# 2_pure60-matrix.net
KiCad netlist of a schematic drawn in Altium Designer
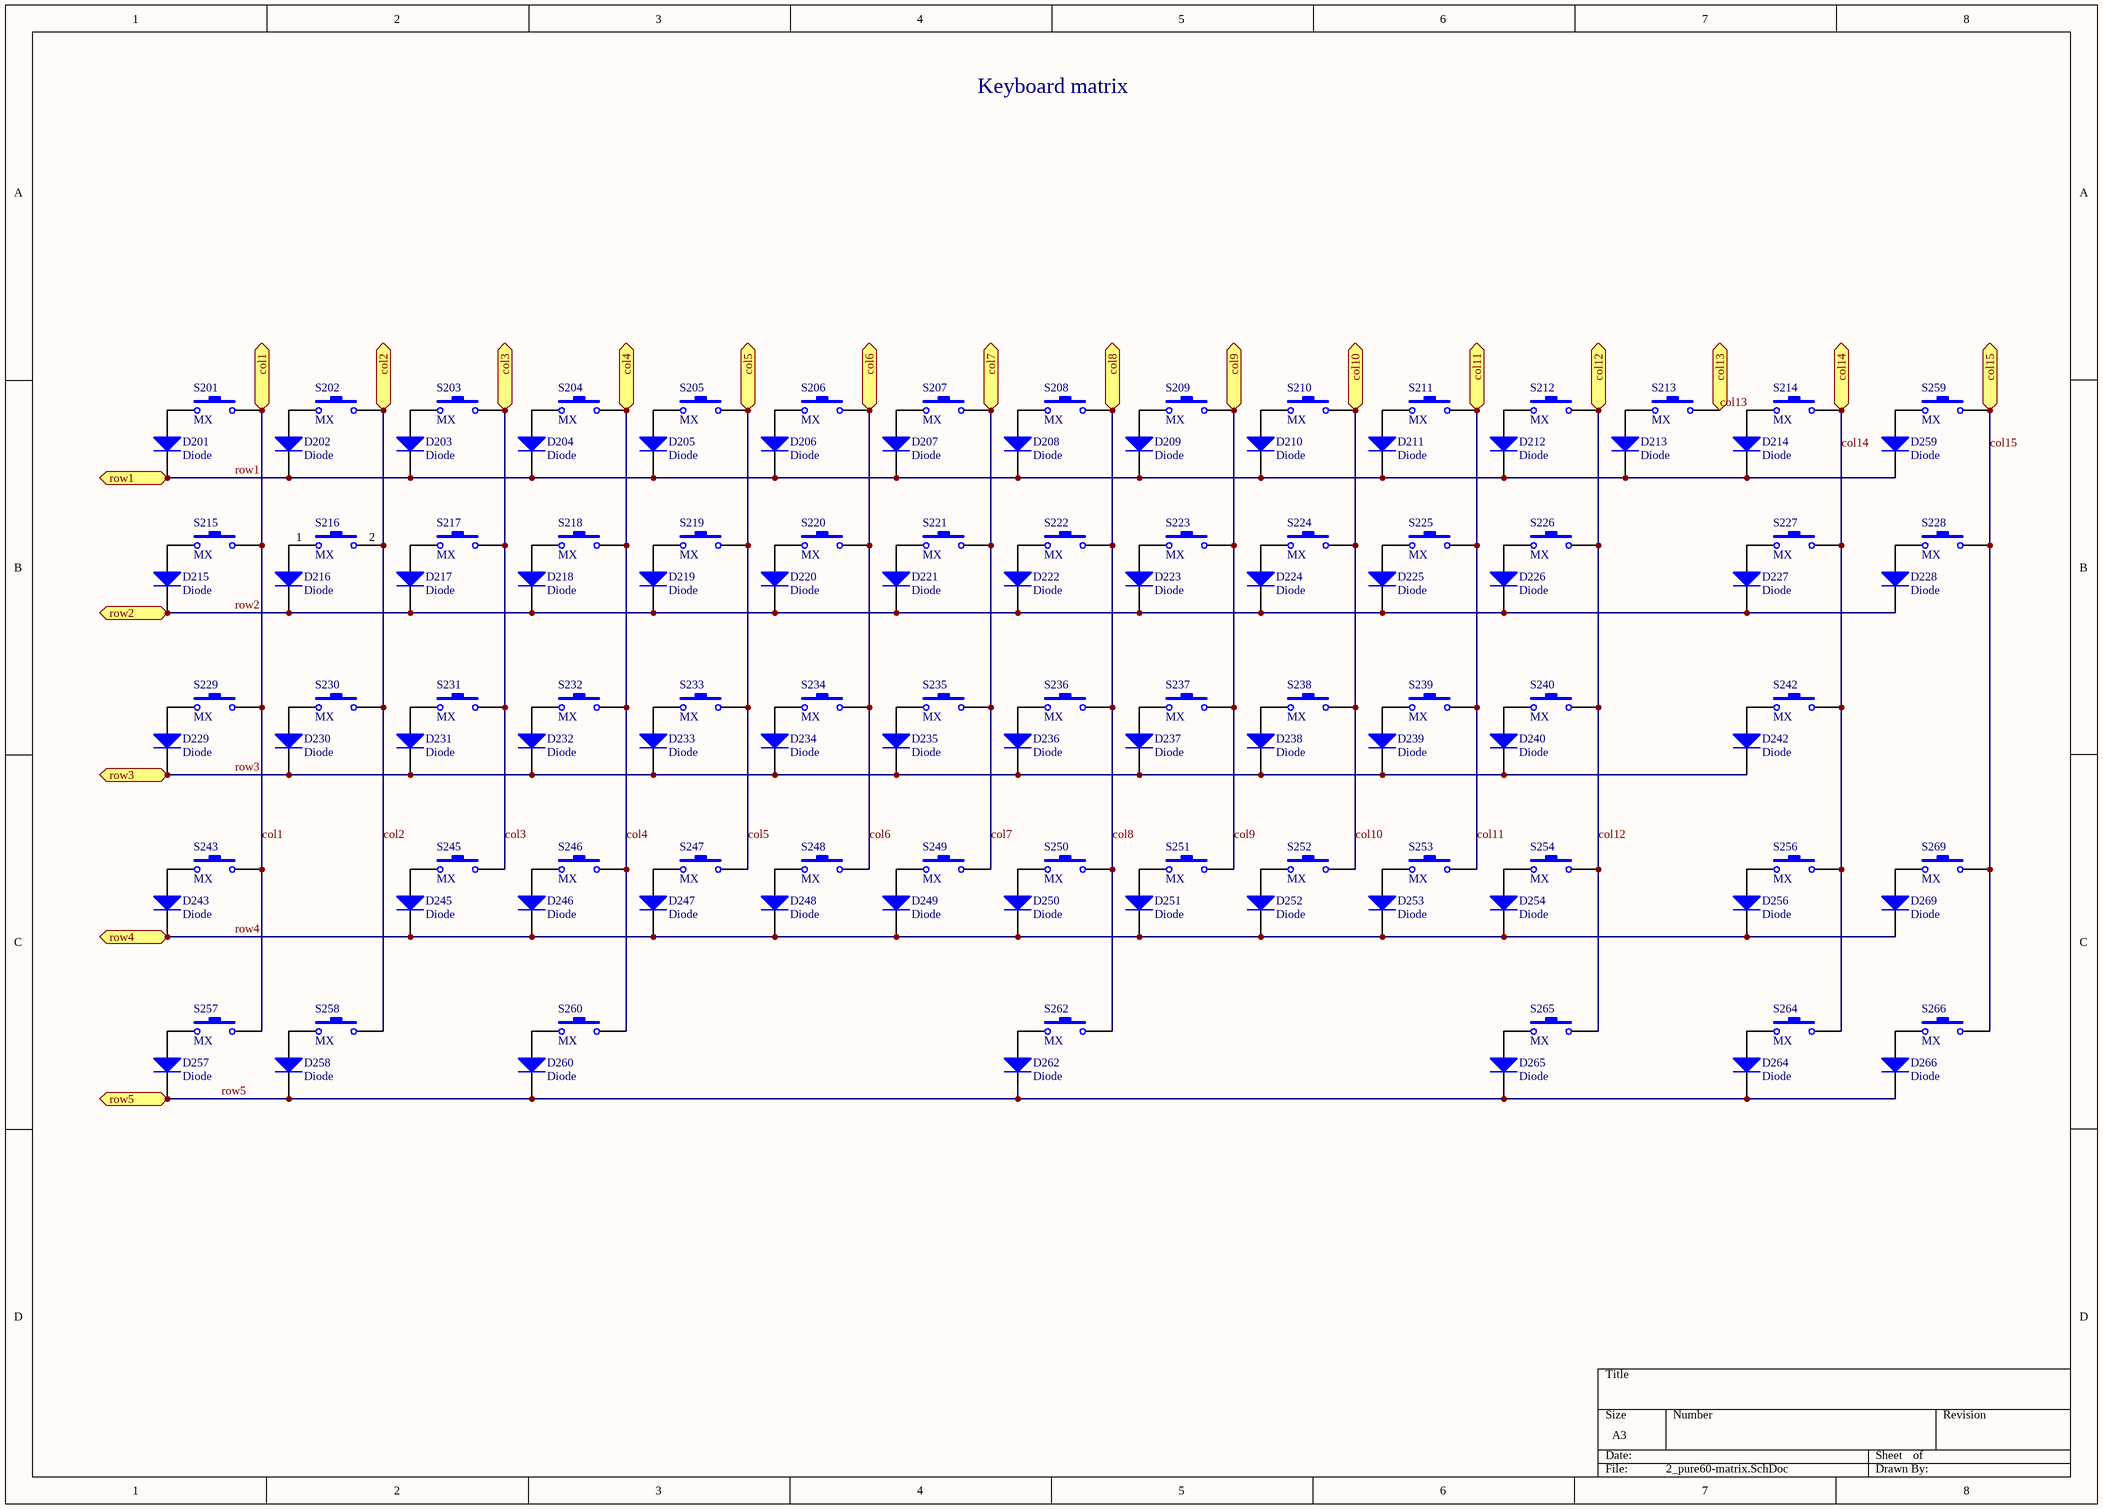
[diagram p0: 2_pure60-matrix.SchDoc]

(export (version "E")
  (design (tool "Eeschema 10.0.6"))
  (components
    (comp (ref "D201")
      (value "Diode")
      (footprint "D0603[1608]")
      (description "Default Diode")
      (fields (field (name "MFG") "Bourns Inc.") (field (name "MRF.PART") "CD4148WTP"))
      (libsource (lib "Miscellaneous Devices") (part "Diode"))
    )
    (comp (ref "D202")
      (value "Diode")
      (footprint "D0603[1608]")
      (description "Default Diode")
      (fields (field (name "MFG") "Bourns Inc.") (field (name "MRF.PART") "CD4148WTP"))
      (libsource (lib "Miscellaneous Devices") (part "Diode"))
    )
    (comp (ref "D203")
      (value "Diode")
      (footprint "D0603[1608]")
      (description "Default Diode")
      (fields (field (name "MFG") "Bourns Inc.") (field (name "MRF.PART") "CD4148WTP"))
      (libsource (lib "Miscellaneous Devices") (part "Diode"))
    )
    (comp (ref "D204")
      (value "Diode")
      (footprint "D0603[1608]")
      (description "Default Diode")
      (fields (field (name "MFG") "Bourns Inc.") (field (name "MRF.PART") "CD4148WTP"))
      (libsource (lib "Miscellaneous Devices") (part "Diode"))
    )
    (comp (ref "D205")
      (value "Diode")
      (footprint "D0603[1608]")
      (description "Default Diode")
      (fields (field (name "MFG") "Bourns Inc.") (field (name "MRF.PART") "CD4148WTP"))
      (libsource (lib "Miscellaneous Devices") (part "Diode"))
    )
    (comp (ref "D206")
      (value "Diode")
      (footprint "D0603[1608]")
      (description "Default Diode")
      (fields (field (name "MFG") "Bourns Inc.") (field (name "MRF.PART") "CD4148WTP"))
      (libsource (lib "Miscellaneous Devices") (part "Diode"))
    )
    (comp (ref "D207")
      (value "Diode")
      (footprint "D0603[1608]")
      (description "Default Diode")
      (fields (field (name "MFG") "Bourns Inc.") (field (name "MRF.PART") "CD4148WTP"))
      (libsource (lib "Miscellaneous Devices") (part "Diode"))
    )
    (comp (ref "D208")
      (value "Diode")
      (footprint "D0603[1608]")
      (description "Default Diode")
      (fields (field (name "MFG") "Bourns Inc.") (field (name "MRF.PART") "CD4148WTP"))
      (libsource (lib "Miscellaneous Devices") (part "Diode"))
    )
    (comp (ref "D209")
      (value "Diode")
      (footprint "D0603[1608]")
      (description "Default Diode")
      (fields (field (name "MFG") "Bourns Inc.") (field (name "MRF.PART") "CD4148WTP"))
      (libsource (lib "Miscellaneous Devices") (part "Diode"))
    )
    (comp (ref "D210")
      (value "Diode")
      (footprint "D0603[1608]")
      (description "Default Diode")
      (fields (field (name "MFG") "Bourns Inc.") (field (name "MRF.PART") "CD4148WTP"))
      (libsource (lib "Miscellaneous Devices") (part "Diode"))
    )
    (comp (ref "D211")
      (value "Diode")
      (footprint "D0603[1608]")
      (description "Default Diode")
      (fields (field (name "MFG") "Bourns Inc.") (field (name "MRF.PART") "CD4148WTP"))
      (libsource (lib "Miscellaneous Devices") (part "Diode"))
    )
    (comp (ref "D212")
      (value "Diode")
      (footprint "D0603[1608]")
      (description "Default Diode")
      (fields (field (name "MFG") "Bourns Inc.") (field (name "MRF.PART") "CD4148WTP"))
      (libsource (lib "Miscellaneous Devices") (part "Diode"))
    )
    (comp (ref "D213")
      (value "Diode")
      (footprint "D0603[1608]")
      (description "Default Diode")
      (fields (field (name "MFG") "Bourns Inc.") (field (name "MRF.PART") "CD4148WTP"))
      (libsource (lib "Miscellaneous Devices") (part "Diode"))
    )
    (comp (ref "D214")
      (value "Diode")
      (footprint "D0603[1608]")
      (description "Default Diode")
      (fields (field (name "MFG") "Bourns Inc.") (field (name "MRF.PART") "CD4148WTP"))
      (libsource (lib "Miscellaneous Devices") (part "Diode"))
    )
    (comp (ref "D215")
      (value "Diode")
      (footprint "D0603[1608]")
      (description "Default Diode")
      (fields (field (name "MFG") "Bourns Inc.") (field (name "MRF.PART") "CD4148WTP"))
      (libsource (lib "Miscellaneous Devices") (part "Diode"))
    )
    (comp (ref "D216")
      (value "Diode")
      (footprint "D0603[1608]")
      (description "Default Diode")
      (fields (field (name "MFG") "Bourns Inc.") (field (name "MRF.PART") "CD4148WTP"))
      (libsource (lib "Miscellaneous Devices") (part "Diode"))
    )
    (comp (ref "D217")
      (value "Diode")
      (footprint "D0603[1608]")
      (description "Default Diode")
      (fields (field (name "MFG") "Bourns Inc.") (field (name "MRF.PART") "CD4148WTP"))
      (libsource (lib "Miscellaneous Devices") (part "Diode"))
    )
    (comp (ref "D218")
      (value "Diode")
      (footprint "D0603[1608]")
      (description "Default Diode")
      (fields (field (name "MFG") "Bourns Inc.") (field (name "MRF.PART") "CD4148WTP"))
      (libsource (lib "Miscellaneous Devices") (part "Diode"))
    )
    (comp (ref "D219")
      (value "Diode")
      (footprint "D0603[1608]")
      (description "Default Diode")
      (fields (field (name "MFG") "Bourns Inc.") (field (name "MRF.PART") "CD4148WTP"))
      (libsource (lib "Miscellaneous Devices") (part "Diode"))
    )
    (comp (ref "D220")
      (value "Diode")
      (footprint "D0603[1608]")
      (description "Default Diode")
      (fields (field (name "MFG") "Bourns Inc.") (field (name "MRF.PART") "CD4148WTP"))
      (libsource (lib "Miscellaneous Devices") (part "Diode"))
    )
    (comp (ref "D221")
      (value "Diode")
      (footprint "D0603[1608]")
      (description "Default Diode")
      (fields (field (name "MFG") "Bourns Inc.") (field (name "MRF.PART") "CD4148WTP"))
      (libsource (lib "Miscellaneous Devices") (part "Diode"))
    )
    (comp (ref "D222")
      (value "Diode")
      (footprint "D0603[1608]")
      (description "Default Diode")
      (fields (field (name "MFG") "Bourns Inc.") (field (name "MRF.PART") "CD4148WTP"))
      (libsource (lib "Miscellaneous Devices") (part "Diode"))
    )
    (comp (ref "D223")
      (value "Diode")
      (footprint "D0603[1608]")
      (description "Default Diode")
      (fields (field (name "MFG") "Bourns Inc.") (field (name "MRF.PART") "CD4148WTP"))
      (libsource (lib "Miscellaneous Devices") (part "Diode"))
    )
    (comp (ref "D224")
      (value "Diode")
      (footprint "D0603[1608]")
      (description "Default Diode")
      (fields (field (name "MFG") "Bourns Inc.") (field (name "MRF.PART") "CD4148WTP"))
      (libsource (lib "Miscellaneous Devices") (part "Diode"))
    )
    (comp (ref "D225")
      (value "Diode")
      (footprint "D0603[1608]")
      (description "Default Diode")
      (fields (field (name "MFG") "Bourns Inc.") (field (name "MRF.PART") "CD4148WTP"))
      (libsource (lib "Miscellaneous Devices") (part "Diode"))
    )
    (comp (ref "D226")
      (value "Diode")
      (footprint "D0603[1608]")
      (description "Default Diode")
      (fields (field (name "MFG") "Bourns Inc.") (field (name "MRF.PART") "CD4148WTP"))
      (libsource (lib "Miscellaneous Devices") (part "Diode"))
    )
    (comp (ref "D227")
      (value "Diode")
      (footprint "D0603[1608]")
      (description "Default Diode")
      (fields (field (name "MFG") "Bourns Inc.") (field (name "MRF.PART") "CD4148WTP"))
      (libsource (lib "Miscellaneous Devices") (part "Diode"))
    )
    (comp (ref "D228")
      (value "Diode")
      (footprint "D0603[1608]")
      (description "Default Diode")
      (fields (field (name "MFG") "Bourns Inc.") (field (name "MRF.PART") "CD4148WTP"))
      (libsource (lib "Miscellaneous Devices") (part "Diode"))
    )
    (comp (ref "D229")
      (value "Diode")
      (footprint "D0603[1608]")
      (description "Default Diode")
      (fields (field (name "MFG") "Bourns Inc.") (field (name "MRF.PART") "CD4148WTP"))
      (libsource (lib "Miscellaneous Devices") (part "Diode"))
    )
    (comp (ref "D230")
      (value "Diode")
      (footprint "D0603[1608]")
      (description "Default Diode")
      (fields (field (name "MFG") "Bourns Inc.") (field (name "MRF.PART") "CD4148WTP"))
      (libsource (lib "Miscellaneous Devices") (part "Diode"))
    )
    (comp (ref "D231")
      (value "Diode")
      (footprint "D0603[1608]")
      (description "Default Diode")
      (fields (field (name "MFG") "Bourns Inc.") (field (name "MRF.PART") "CD4148WTP"))
      (libsource (lib "Miscellaneous Devices") (part "Diode"))
    )
    (comp (ref "D232")
      (value "Diode")
      (footprint "D0603[1608]")
      (description "Default Diode")
      (fields (field (name "MFG") "Bourns Inc.") (field (name "MRF.PART") "CD4148WTP"))
      (libsource (lib "Miscellaneous Devices") (part "Diode"))
    )
    (comp (ref "D233")
      (value "Diode")
      (footprint "D0603[1608]")
      (description "Default Diode")
      (fields (field (name "MFG") "Bourns Inc.") (field (name "MRF.PART") "CD4148WTP"))
      (libsource (lib "Miscellaneous Devices") (part "Diode"))
    )
    (comp (ref "D234")
      (value "Diode")
      (footprint "D0603[1608]")
      (description "Default Diode")
      (fields (field (name "MFG") "Bourns Inc.") (field (name "MRF.PART") "CD4148WTP"))
      (libsource (lib "Miscellaneous Devices") (part "Diode"))
    )
    (comp (ref "D235")
      (value "Diode")
      (footprint "D0603[1608]")
      (description "Default Diode")
      (fields (field (name "MFG") "Bourns Inc.") (field (name "MRF.PART") "CD4148WTP"))
      (libsource (lib "Miscellaneous Devices") (part "Diode"))
    )
    (comp (ref "D236")
      (value "Diode")
      (footprint "D0603[1608]")
      (description "Default Diode")
      (fields (field (name "MFG") "Bourns Inc.") (field (name "MRF.PART") "CD4148WTP"))
      (libsource (lib "Miscellaneous Devices") (part "Diode"))
    )
    (comp (ref "D237")
      (value "Diode")
      (footprint "D0603[1608]")
      (description "Default Diode")
      (fields (field (name "MFG") "Bourns Inc.") (field (name "MRF.PART") "CD4148WTP"))
      (libsource (lib "Miscellaneous Devices") (part "Diode"))
    )
    (comp (ref "D238")
      (value "Diode")
      (footprint "D0603[1608]")
      (description "Default Diode")
      (fields (field (name "MFG") "Bourns Inc.") (field (name "MRF.PART") "CD4148WTP"))
      (libsource (lib "Miscellaneous Devices") (part "Diode"))
    )
    (comp (ref "D239")
      (value "Diode")
      (footprint "D0603[1608]")
      (description "Default Diode")
      (fields (field (name "MFG") "Bourns Inc.") (field (name "MRF.PART") "CD4148WTP"))
      (libsource (lib "Miscellaneous Devices") (part "Diode"))
    )
    (comp (ref "D240")
      (value "Diode")
      (footprint "D0603[1608]")
      (description "Default Diode")
      (fields (field (name "MFG") "Bourns Inc.") (field (name "MRF.PART") "CD4148WTP"))
      (libsource (lib "Miscellaneous Devices") (part "Diode"))
    )
    (comp (ref "D242")
      (value "Diode")
      (footprint "D0603[1608]")
      (description "Default Diode")
      (fields (field (name "MFG") "Bourns Inc.") (field (name "MRF.PART") "CD4148WTP"))
      (libsource (lib "Miscellaneous Devices") (part "Diode"))
    )
    (comp (ref "D243")
      (value "Diode")
      (footprint "D0603[1608]")
      (description "Default Diode")
      (fields (field (name "MFG") "Bourns Inc.") (field (name "MRF.PART") "CD4148WTP"))
      (libsource (lib "Miscellaneous Devices") (part "Diode"))
    )
    (comp (ref "D245")
      (value "Diode")
      (footprint "D0603[1608]")
      (description "Default Diode")
      (fields (field (name "MFG") "Bourns Inc.") (field (name "MRF.PART") "CD4148WTP"))
      (libsource (lib "Miscellaneous Devices") (part "Diode"))
    )
    (comp (ref "D246")
      (value "Diode")
      (footprint "D0603[1608]")
      (description "Default Diode")
      (fields (field (name "MFG") "Bourns Inc.") (field (name "MRF.PART") "CD4148WTP"))
      (libsource (lib "Miscellaneous Devices") (part "Diode"))
    )
    (comp (ref "D247")
      (value "Diode")
      (footprint "D0603[1608]")
      (description "Default Diode")
      (fields (field (name "MFG") "Bourns Inc.") (field (name "MRF.PART") "CD4148WTP"))
      (libsource (lib "Miscellaneous Devices") (part "Diode"))
    )
    (comp (ref "D248")
      (value "Diode")
      (footprint "D0603[1608]")
      (description "Default Diode")
      (fields (field (name "MFG") "Bourns Inc.") (field (name "MRF.PART") "CD4148WTP"))
      (libsource (lib "Miscellaneous Devices") (part "Diode"))
    )
    (comp (ref "D249")
      (value "Diode")
      (footprint "D0603[1608]")
      (description "Default Diode")
      (fields (field (name "MFG") "Bourns Inc.") (field (name "MRF.PART") "CD4148WTP"))
      (libsource (lib "Miscellaneous Devices") (part "Diode"))
    )
    (comp (ref "D250")
      (value "Diode")
      (footprint "D0603[1608]")
      (description "Default Diode")
      (fields (field (name "MFG") "Bourns Inc.") (field (name "MRF.PART") "CD4148WTP"))
      (libsource (lib "Miscellaneous Devices") (part "Diode"))
    )
    (comp (ref "D251")
      (value "Diode")
      (footprint "D0603[1608]")
      (description "Default Diode")
      (fields (field (name "MFG") "Bourns Inc.") (field (name "MRF.PART") "CD4148WTP"))
      (libsource (lib "Miscellaneous Devices") (part "Diode"))
    )
    (comp (ref "D252")
      (value "Diode")
      (footprint "D0603[1608]")
      (description "Default Diode")
      (fields (field (name "MFG") "Bourns Inc.") (field (name "MRF.PART") "CD4148WTP"))
      (libsource (lib "Miscellaneous Devices") (part "Diode"))
    )
    (comp (ref "D253")
      (value "Diode")
      (footprint "D0603[1608]")
      (description "Default Diode")
      (fields (field (name "MFG") "Bourns Inc.") (field (name "MRF.PART") "CD4148WTP"))
      (libsource (lib "Miscellaneous Devices") (part "Diode"))
    )
    (comp (ref "D254")
      (value "Diode")
      (footprint "D0603[1608]")
      (description "Default Diode")
      (fields (field (name "MFG") "Bourns Inc.") (field (name "MRF.PART") "CD4148WTP"))
      (libsource (lib "Miscellaneous Devices") (part "Diode"))
    )
    (comp (ref "D256")
      (value "Diode")
      (footprint "D0603[1608]")
      (description "Default Diode")
      (fields (field (name "MFG") "Bourns Inc.") (field (name "MRF.PART") "CD4148WTP"))
      (libsource (lib "Miscellaneous Devices") (part "Diode"))
    )
    (comp (ref "D257")
      (value "Diode")
      (footprint "D0603[1608]")
      (description "Default Diode")
      (fields (field (name "MFG") "Bourns Inc.") (field (name "MRF.PART") "CD4148WTP"))
      (libsource (lib "Miscellaneous Devices") (part "Diode"))
    )
    (comp (ref "D258")
      (value "Diode")
      (footprint "D0603[1608]")
      (description "Default Diode")
      (fields (field (name "MFG") "Bourns Inc.") (field (name "MRF.PART") "CD4148WTP"))
      (libsource (lib "Miscellaneous Devices") (part "Diode"))
    )
    (comp (ref "D259")
      (value "Diode")
      (footprint "D0603[1608]")
      (description "Default Diode")
      (fields (field (name "MFG") "Bourns Inc.") (field (name "MRF.PART") "CD4148WTP"))
      (libsource (lib "Miscellaneous Devices") (part "Diode"))
    )
    (comp (ref "D260")
      (value "Diode")
      (footprint "D0603[1608]")
      (description "Default Diode")
      (fields (field (name "MFG") "Bourns Inc.") (field (name "MRF.PART") "CD4148WTP"))
      (libsource (lib "Miscellaneous Devices") (part "Diode"))
    )
    (comp (ref "D262")
      (value "Diode")
      (footprint "D0603[1608]")
      (description "Default Diode")
      (fields (field (name "MFG") "Bourns Inc.") (field (name "MRF.PART") "CD4148WTP"))
      (libsource (lib "Miscellaneous Devices") (part "Diode"))
    )
    (comp (ref "D264")
      (value "Diode")
      (footprint "D0603[1608]")
      (description "Default Diode")
      (fields (field (name "MFG") "Bourns Inc.") (field (name "MRF.PART") "CD4148WTP"))
      (libsource (lib "Miscellaneous Devices") (part "Diode"))
    )
    (comp (ref "D265")
      (value "Diode")
      (footprint "D0603[1608]")
      (description "Default Diode")
      (fields (field (name "MFG") "Bourns Inc.") (field (name "MRF.PART") "CD4148WTP"))
      (libsource (lib "Miscellaneous Devices") (part "Diode"))
    )
    (comp (ref "D266")
      (value "Diode")
      (footprint "D0603[1608]")
      (description "Default Diode")
      (fields (field (name "MFG") "Bourns Inc.") (field (name "MRF.PART") "CD4148WTP"))
      (libsource (lib "Miscellaneous Devices") (part "Diode"))
    )
    (comp (ref "D269")
      (value "Diode")
      (footprint "D0603[1608]")
      (description "Default Diode")
      (fields (field (name "MFG") "Bourns Inc.") (field (name "MRF.PART") "CD4148WTP"))
      (libsource (lib "Miscellaneous Devices") (part "Diode"))
    )
    (comp (ref "S201")
      (value "MX")
      (footprint "MX-switch - switched pol")
      (description "Switch")
      (libsource (lib "Miscellaneous Devices") (part "SW-PB"))
    )
    (comp (ref "S202")
      (value "MX")
      (footprint "MX-switch - switched pol")
      (description "Switch")
      (libsource (lib "Miscellaneous Devices") (part "SW-PB"))
    )
    (comp (ref "S203")
      (value "MX")
      (footprint "MX-switch - switched pol")
      (description "Switch")
      (libsource (lib "Miscellaneous Devices") (part "SW-PB"))
    )
    (comp (ref "S204")
      (value "MX")
      (footprint "MX-switch - switched pol")
      (description "Switch")
      (libsource (lib "Miscellaneous Devices") (part "SW-PB"))
    )
    (comp (ref "S205")
      (value "MX")
      (footprint "MX-switch - switched pol")
      (description "Switch")
      (libsource (lib "Miscellaneous Devices") (part "SW-PB"))
    )
    (comp (ref "S206")
      (value "MX")
      (footprint "MX-switch - switched pol")
      (description "Switch")
      (libsource (lib "Miscellaneous Devices") (part "SW-PB"))
    )
    (comp (ref "S207")
      (value "MX")
      (footprint "MX-switch - switched pol")
      (description "Switch")
      (libsource (lib "Miscellaneous Devices") (part "SW-PB"))
    )
    (comp (ref "S208")
      (value "MX")
      (footprint "MX-switch - switched pol")
      (description "Switch")
      (libsource (lib "Miscellaneous Devices") (part "SW-PB"))
    )
    (comp (ref "S209")
      (value "MX")
      (footprint "MX-switch - switched pol")
      (description "Switch")
      (libsource (lib "Miscellaneous Devices") (part "SW-PB"))
    )
    (comp (ref "S210")
      (value "MX")
      (footprint "MX-switch - switched pol")
      (description "Switch")
      (libsource (lib "Miscellaneous Devices") (part "SW-PB"))
    )
    (comp (ref "S211")
      (value "MX")
      (footprint "MX-switch - switched pol")
      (description "Switch")
      (libsource (lib "Miscellaneous Devices") (part "SW-PB"))
    )
    (comp (ref "S212")
      (value "MX")
      (footprint "MX-switch - switched pol")
      (description "Switch")
      (libsource (lib "Miscellaneous Devices") (part "SW-PB"))
    )
    (comp (ref "S213")
      (value "MX")
      (footprint "MX-switch - switched pol")
      (description "Switch")
      (libsource (lib "Miscellaneous Devices") (part "SW-PB"))
    )
    (comp (ref "S214")
      (value "MX")
      (footprint "MX-switch - switched pol")
      (description "Switch")
      (libsource (lib "Miscellaneous Devices") (part "SW-PB"))
    )
    (comp (ref "S215")
      (value "MX")
      (footprint "MX-switch - 1.5U - switched pol")
      (description "TAB")
      (libsource (lib "Miscellaneous Devices") (part "SW-PB"))
    )
    (comp (ref "S216")
      (value "MX")
      (footprint "MX-switch - switched pol")
      (description "Switch")
      (libsource (lib "") (part "SW-PB_1"))
    )
    (comp (ref "S217")
      (value "MX")
      (footprint "MX-switch - switched pol")
      (description "Switch")
      (libsource (lib "Miscellaneous Devices") (part "SW-PB"))
    )
    (comp (ref "S218")
      (value "MX")
      (footprint "MX-switch - switched pol")
      (description "Switch")
      (libsource (lib "Miscellaneous Devices") (part "SW-PB"))
    )
    (comp (ref "S219")
      (value "MX")
      (footprint "MX-switch - switched pol")
      (description "Switch")
      (libsource (lib "Miscellaneous Devices") (part "SW-PB"))
    )
    (comp (ref "S220")
      (value "MX")
      (footprint "MX-switch - switched pol")
      (description "Switch")
      (libsource (lib "Miscellaneous Devices") (part "SW-PB"))
    )
    (comp (ref "S221")
      (value "MX")
      (footprint "MX-switch - switched pol")
      (description "Switch")
      (libsource (lib "Miscellaneous Devices") (part "SW-PB"))
    )
    (comp (ref "S222")
      (value "MX")
      (footprint "MX-switch - switched pol")
      (description "Switch")
      (libsource (lib "Miscellaneous Devices") (part "SW-PB"))
    )
    (comp (ref "S223")
      (value "MX")
      (footprint "MX-switch - switched pol")
      (description "Switch")
      (libsource (lib "Miscellaneous Devices") (part "SW-PB"))
    )
    (comp (ref "S224")
      (value "MX")
      (footprint "MX-switch - switched pol")
      (description "Switch")
      (libsource (lib "Miscellaneous Devices") (part "SW-PB"))
    )
    (comp (ref "S225")
      (value "MX")
      (footprint "MX-switch - switched pol")
      (description "Switch")
      (libsource (lib "Miscellaneous Devices") (part "SW-PB"))
    )
    (comp (ref "S226")
      (value "MX")
      (footprint "MX-switch - switched pol")
      (description "Switch")
      (libsource (lib "Miscellaneous Devices") (part "SW-PB"))
    )
    (comp (ref "S227")
      (value "MX")
      (footprint "MX-switch - switched pol")
      (description "Switch")
      (libsource (lib "Miscellaneous Devices") (part "SW-PB"))
    )
    (comp (ref "S228")
      (value "MX")
      (footprint "MX-switch - 1.5U")
      (description "Switch")
      (libsource (lib "Miscellaneous Devices") (part "SW-PB"))
    )
    (comp (ref "S229")
      (value "MX")
      (footprint "MX-switch - CAPS - stepped")
      (description "Switch")
      (libsource (lib "Miscellaneous Devices") (part "SW-PB"))
    )
    (comp (ref "S230")
      (value "MX")
      (footprint "MX-switch - switched pol")
      (description "Switch")
      (libsource (lib "Miscellaneous Devices") (part "SW-PB"))
    )
    (comp (ref "S231")
      (value "MX")
      (footprint "MX-switch - switched pol")
      (description "Switch")
      (libsource (lib "Miscellaneous Devices") (part "SW-PB"))
    )
    (comp (ref "S232")
      (value "MX")
      (footprint "MX-switch - switched pol")
      (description "Switch")
      (libsource (lib "Miscellaneous Devices") (part "SW-PB"))
    )
    (comp (ref "S233")
      (value "MX")
      (footprint "MX-switch - switched pol")
      (description "Switch")
      (libsource (lib "Miscellaneous Devices") (part "SW-PB"))
    )
    (comp (ref "S234")
      (value "MX")
      (footprint "MX-switch - switched pol")
      (description "Switch")
      (libsource (lib "Miscellaneous Devices") (part "SW-PB"))
    )
    (comp (ref "S235")
      (value "MX")
      (footprint "MX-switch - switched pol")
      (description "Switch")
      (libsource (lib "Miscellaneous Devices") (part "SW-PB"))
    )
    (comp (ref "S236")
      (value "MX")
      (footprint "MX-switch - switched pol")
      (description "Switch")
      (libsource (lib "Miscellaneous Devices") (part "SW-PB"))
    )
    (comp (ref "S237")
      (value "MX")
      (footprint "MX-switch - switched pol")
      (description "Switch")
      (libsource (lib "Miscellaneous Devices") (part "SW-PB"))
    )
    (comp (ref "S238")
      (value "MX")
      (footprint "MX-switch - switched pol")
      (description "Switch")
      (libsource (lib "Miscellaneous Devices") (part "SW-PB"))
    )
    (comp (ref "S239")
      (value "MX")
      (footprint "MX-switch - switched pol")
      (description "Switch")
      (libsource (lib "Miscellaneous Devices") (part "SW-PB"))
    )
    (comp (ref "S240")
      (value "MX")
      (footprint "MX-switch - switched pol")
      (description "Switch")
      (libsource (lib "Miscellaneous Devices") (part "SW-PB"))
    )
    (comp (ref "S242")
      (value "MX")
      (footprint "MX-switch - Enter_ANSI")
      (description "Switch")
      (libsource (lib "Miscellaneous Devices") (part "SW-PB"))
    )
    (comp (ref "S243")
      (value "MX")
      (footprint "MX-switch - 2.25U")
      (description "Switch")
      (libsource (lib "Miscellaneous Devices") (part "SW-PB"))
    )
    (comp (ref "S245")
      (value "MX")
      (footprint "MX-switch - switched pol")
      (description "Switch")
      (libsource (lib "Miscellaneous Devices") (part "SW-PB"))
    )
    (comp (ref "S246")
      (value "MX")
      (footprint "MX-switch - switched pol")
      (description "Switch")
      (libsource (lib "Miscellaneous Devices") (part "SW-PB"))
    )
    (comp (ref "S247")
      (value "MX")
      (footprint "MX-switch - switched pol")
      (description "Switch")
      (libsource (lib "Miscellaneous Devices") (part "SW-PB"))
    )
    (comp (ref "S248")
      (value "MX")
      (footprint "MX-switch - switched pol")
      (description "Switch")
      (libsource (lib "Miscellaneous Devices") (part "SW-PB"))
    )
    (comp (ref "S249")
      (value "MX")
      (footprint "MX-switch - switched pol")
      (description "Switch")
      (libsource (lib "Miscellaneous Devices") (part "SW-PB"))
    )
    (comp (ref "S250")
      (value "MX")
      (footprint "MX-switch - switched pol")
      (description "Switch")
      (libsource (lib "Miscellaneous Devices") (part "SW-PB"))
    )
    (comp (ref "S251")
      (value "MX")
      (footprint "MX-switch - switched pol")
      (description "Switch")
      (libsource (lib "Miscellaneous Devices") (part "SW-PB"))
    )
    (comp (ref "S252")
      (value "MX")
      (footprint "MX-switch - switched pol")
      (description "Switch")
      (libsource (lib "Miscellaneous Devices") (part "SW-PB"))
    )
    (comp (ref "S253")
      (value "MX")
      (footprint "MX-switch - switched pol")
      (description "Switch")
      (libsource (lib "Miscellaneous Devices") (part "SW-PB"))
    )
    (comp (ref "S254")
      (value "MX")
      (footprint "MX-switch - switched pol")
      (description "Switch")
      (libsource (lib "Miscellaneous Devices") (part "SW-PB"))
    )
    (comp (ref "S256")
      (value "MX")
      (footprint "MX-switch - 1.75")
      (description "Switch")
      (libsource (lib "Miscellaneous Devices") (part "SW-PB"))
    )
    (comp (ref "S257")
      (value "MX")
      (footprint "MX-switch - 1.5U")
      (description "Switch")
      (libsource (lib "Miscellaneous Devices") (part "SW-PB"))
    )
    (comp (ref "S258")
      (value "MX")
      (footprint "MX-switch")
      (description "Switch")
      (libsource (lib "Miscellaneous Devices") (part "SW-PB"))
    )
    (comp (ref "S259")
      (value "MX")
      (footprint "MX-switch")
      (description "Switch")
      (libsource (lib "Miscellaneous Devices") (part "SW-PB"))
    )
    (comp (ref "S260")
      (value "MX")
      (footprint "MX-switch - 1.5U")
      (description "Switch")
      (libsource (lib "Miscellaneous Devices") (part "SW-PB"))
    )
    (comp (ref "S262")
      (value "MX")
      (footprint "MX-switch - 7u space")
      (description "Switch")
      (libsource (lib "Miscellaneous Devices") (part "SW-PB"))
    )
    (comp (ref "S264")
      (value "MX")
      (footprint "MX-switch")
      (description "Switch")
      (libsource (lib "Miscellaneous Devices") (part "SW-PB"))
    )
    (comp (ref "S265")
      (value "MX")
      (footprint "MX-switch - 1.5U")
      (description "Switch")
      (libsource (lib "Miscellaneous Devices") (part "SW-PB"))
    )
    (comp (ref "S266")
      (value "MX")
      (footprint "MX-switch - 1.5U")
      (description "Switch")
      (libsource (lib "Miscellaneous Devices") (part "SW-PB"))
    )
    (comp (ref "S269")
      (value "MX")
      (footprint "MX-switch")
      (description "Switch")
      (libsource (lib "Miscellaneous Devices") (part "SW-PB"))
    )
  )
  (nets
    (net (code "1") (name "/col1") (class "Default")
      (node (ref "S201") (pin "2") (pinfunction "2_2") (pintype "passive"))
      (node (ref "S215") (pin "2") (pinfunction "2_2") (pintype "passive"))
      (node (ref "S229") (pin "2") (pinfunction "2_2") (pintype "passive"))
      (node (ref "S243") (pin "2") (pinfunction "2_2") (pintype "passive"))
      (node (ref "S257") (pin "2") (pinfunction "2_2") (pintype "passive"))
    )
    (net (code "2") (name "/col2") (class "Default")
      (node (ref "S202") (pin "2") (pinfunction "2_2") (pintype "passive"))
      (node (ref "S216") (pin "2") (pinfunction "2_2") (pintype "passive"))
      (node (ref "S230") (pin "2") (pinfunction "2_2") (pintype "passive"))
      (node (ref "S258") (pin "2") (pinfunction "2_2") (pintype "passive"))
    )
    (net (code "3") (name "/col3") (class "Default")
      (node (ref "S203") (pin "2") (pinfunction "2_2") (pintype "passive"))
      (node (ref "S217") (pin "2") (pinfunction "2_2") (pintype "passive"))
      (node (ref "S231") (pin "2") (pinfunction "2_2") (pintype "passive"))
      (node (ref "S245") (pin "2") (pinfunction "2_2") (pintype "passive"))
    )
    (net (code "4") (name "/col4") (class "Default")
      (node (ref "S204") (pin "2") (pinfunction "2_2") (pintype "passive"))
      (node (ref "S218") (pin "2") (pinfunction "2_2") (pintype "passive"))
      (node (ref "S232") (pin "2") (pinfunction "2_2") (pintype "passive"))
      (node (ref "S246") (pin "2") (pinfunction "2_2") (pintype "passive"))
      (node (ref "S260") (pin "2") (pinfunction "2_2") (pintype "passive"))
    )
    (net (code "5") (name "/col5") (class "Default")
      (node (ref "S205") (pin "2") (pinfunction "2_2") (pintype "passive"))
      (node (ref "S219") (pin "2") (pinfunction "2_2") (pintype "passive"))
      (node (ref "S233") (pin "2") (pinfunction "2_2") (pintype "passive"))
      (node (ref "S247") (pin "2") (pinfunction "2_2") (pintype "passive"))
    )
    (net (code "6") (name "/col6") (class "Default")
      (node (ref "S206") (pin "2") (pinfunction "2_2") (pintype "passive"))
      (node (ref "S220") (pin "2") (pinfunction "2_2") (pintype "passive"))
      (node (ref "S234") (pin "2") (pinfunction "2_2") (pintype "passive"))
      (node (ref "S248") (pin "2") (pinfunction "2_2") (pintype "passive"))
    )
    (net (code "7") (name "/col7") (class "Default")
      (node (ref "S207") (pin "2") (pinfunction "2_2") (pintype "passive"))
      (node (ref "S221") (pin "2") (pinfunction "2_2") (pintype "passive"))
      (node (ref "S235") (pin "2") (pinfunction "2_2") (pintype "passive"))
      (node (ref "S249") (pin "2") (pinfunction "2_2") (pintype "passive"))
    )
    (net (code "8") (name "/col8") (class "Default")
      (node (ref "S208") (pin "2") (pinfunction "2_2") (pintype "passive"))
      (node (ref "S222") (pin "2") (pinfunction "2_2") (pintype "passive"))
      (node (ref "S236") (pin "2") (pinfunction "2_2") (pintype "passive"))
      (node (ref "S250") (pin "2") (pinfunction "2_2") (pintype "passive"))
      (node (ref "S262") (pin "2") (pinfunction "2_2") (pintype "passive"))
    )
    (net (code "9") (name "/col9") (class "Default")
      (node (ref "S209") (pin "2") (pinfunction "2_2") (pintype "passive"))
      (node (ref "S223") (pin "2") (pinfunction "2_2") (pintype "passive"))
      (node (ref "S237") (pin "2") (pinfunction "2_2") (pintype "passive"))
      (node (ref "S251") (pin "2") (pinfunction "2_2") (pintype "passive"))
    )
    (net (code "10") (name "/col10") (class "Default")
      (node (ref "S210") (pin "2") (pinfunction "2_2") (pintype "passive"))
      (node (ref "S224") (pin "2") (pinfunction "2_2") (pintype "passive"))
      (node (ref "S238") (pin "2") (pinfunction "2_2") (pintype "passive"))
      (node (ref "S252") (pin "2") (pinfunction "2_2") (pintype "passive"))
    )
    (net (code "11") (name "/col11") (class "Default")
      (node (ref "S211") (pin "2") (pinfunction "2_2") (pintype "passive"))
      (node (ref "S225") (pin "2") (pinfunction "2_2") (pintype "passive"))
      (node (ref "S239") (pin "2") (pinfunction "2_2") (pintype "passive"))
      (node (ref "S253") (pin "2") (pinfunction "2_2") (pintype "passive"))
    )
    (net (code "12") (name "/col12") (class "Default")
      (node (ref "S212") (pin "2") (pinfunction "2_2") (pintype "passive"))
      (node (ref "S226") (pin "2") (pinfunction "2_2") (pintype "passive"))
      (node (ref "S240") (pin "2") (pinfunction "2_2") (pintype "passive"))
      (node (ref "S254") (pin "2") (pinfunction "2_2") (pintype "passive"))
      (node (ref "S265") (pin "2") (pinfunction "2_2") (pintype "passive"))
    )
    (net (code "13") (name "/col13") (class "Default")
      (node (ref "S213") (pin "2") (pinfunction "2_2") (pintype "passive"))
    )
    (net (code "14") (name "/col14") (class "Default")
      (node (ref "S214") (pin "2") (pinfunction "2_2") (pintype "passive"))
      (node (ref "S227") (pin "2") (pinfunction "2_2") (pintype "passive"))
      (node (ref "S242") (pin "2") (pinfunction "2_2") (pintype "passive"))
      (node (ref "S256") (pin "2") (pinfunction "2_2") (pintype "passive"))
      (node (ref "S264") (pin "2") (pinfunction "2_2") (pintype "passive"))
    )
    (net (code "15") (name "/col15") (class "Default")
      (node (ref "S228") (pin "2") (pinfunction "2_2") (pintype "passive"))
      (node (ref "S259") (pin "2") (pinfunction "2_2") (pintype "passive"))
      (node (ref "S266") (pin "2") (pinfunction "2_2") (pintype "passive"))
      (node (ref "S269") (pin "2") (pinfunction "2_2") (pintype "passive"))
    )
    (net (code "16") (name "/row1") (class "Default")
      (node (ref "D201") (pin "2") (pinfunction "K_2") (pintype "passive"))
      (node (ref "D202") (pin "2") (pinfunction "K_2") (pintype "passive"))
      (node (ref "D203") (pin "2") (pinfunction "K_2") (pintype "passive"))
      (node (ref "D204") (pin "2") (pinfunction "K_2") (pintype "passive"))
      (node (ref "D205") (pin "2") (pinfunction "K_2") (pintype "passive"))
      (node (ref "D206") (pin "2") (pinfunction "K_2") (pintype "passive"))
      (node (ref "D207") (pin "2") (pinfunction "K_2") (pintype "passive"))
      (node (ref "D208") (pin "2") (pinfunction "K_2") (pintype "passive"))
      (node (ref "D209") (pin "2") (pinfunction "K_2") (pintype "passive"))
      (node (ref "D210") (pin "2") (pinfunction "K_2") (pintype "passive"))
      (node (ref "D211") (pin "2") (pinfunction "K_2") (pintype "passive"))
      (node (ref "D212") (pin "2") (pinfunction "K_2") (pintype "passive"))
      (node (ref "D213") (pin "2") (pinfunction "K_2") (pintype "passive"))
      (node (ref "D214") (pin "2") (pinfunction "K_2") (pintype "passive"))
      (node (ref "D259") (pin "2") (pinfunction "K_2") (pintype "passive"))
    )
    (net (code "17") (name "/row2") (class "Default")
      (node (ref "D215") (pin "2") (pinfunction "K_2") (pintype "passive"))
      (node (ref "D216") (pin "2") (pinfunction "K_2") (pintype "passive"))
      (node (ref "D217") (pin "2") (pinfunction "K_2") (pintype "passive"))
      (node (ref "D218") (pin "2") (pinfunction "K_2") (pintype "passive"))
      (node (ref "D219") (pin "2") (pinfunction "K_2") (pintype "passive"))
      (node (ref "D220") (pin "2") (pinfunction "K_2") (pintype "passive"))
      (node (ref "D221") (pin "2") (pinfunction "K_2") (pintype "passive"))
      (node (ref "D222") (pin "2") (pinfunction "K_2") (pintype "passive"))
      (node (ref "D223") (pin "2") (pinfunction "K_2") (pintype "passive"))
      (node (ref "D224") (pin "2") (pinfunction "K_2") (pintype "passive"))
      (node (ref "D225") (pin "2") (pinfunction "K_2") (pintype "passive"))
      (node (ref "D226") (pin "2") (pinfunction "K_2") (pintype "passive"))
      (node (ref "D227") (pin "2") (pinfunction "K_2") (pintype "passive"))
      (node (ref "D228") (pin "2") (pinfunction "K_2") (pintype "passive"))
    )
    (net (code "18") (name "/row3") (class "Default")
      (node (ref "D229") (pin "2") (pinfunction "K_2") (pintype "passive"))
      (node (ref "D230") (pin "2") (pinfunction "K_2") (pintype "passive"))
      (node (ref "D231") (pin "2") (pinfunction "K_2") (pintype "passive"))
      (node (ref "D232") (pin "2") (pinfunction "K_2") (pintype "passive"))
      (node (ref "D233") (pin "2") (pinfunction "K_2") (pintype "passive"))
      (node (ref "D234") (pin "2") (pinfunction "K_2") (pintype "passive"))
      (node (ref "D235") (pin "2") (pinfunction "K_2") (pintype "passive"))
      (node (ref "D236") (pin "2") (pinfunction "K_2") (pintype "passive"))
      (node (ref "D237") (pin "2") (pinfunction "K_2") (pintype "passive"))
      (node (ref "D238") (pin "2") (pinfunction "K_2") (pintype "passive"))
      (node (ref "D239") (pin "2") (pinfunction "K_2") (pintype "passive"))
      (node (ref "D240") (pin "2") (pinfunction "K_2") (pintype "passive"))
      (node (ref "D242") (pin "2") (pinfunction "K_2") (pintype "passive"))
    )
    (net (code "19") (name "/row4") (class "Default")
      (node (ref "D243") (pin "2") (pinfunction "K_2") (pintype "passive"))
      (node (ref "D245") (pin "2") (pinfunction "K_2") (pintype "passive"))
      (node (ref "D246") (pin "2") (pinfunction "K_2") (pintype "passive"))
      (node (ref "D247") (pin "2") (pinfunction "K_2") (pintype "passive"))
      (node (ref "D248") (pin "2") (pinfunction "K_2") (pintype "passive"))
      (node (ref "D249") (pin "2") (pinfunction "K_2") (pintype "passive"))
      (node (ref "D250") (pin "2") (pinfunction "K_2") (pintype "passive"))
      (node (ref "D251") (pin "2") (pinfunction "K_2") (pintype "passive"))
      (node (ref "D252") (pin "2") (pinfunction "K_2") (pintype "passive"))
      (node (ref "D253") (pin "2") (pinfunction "K_2") (pintype "passive"))
      (node (ref "D254") (pin "2") (pinfunction "K_2") (pintype "passive"))
      (node (ref "D256") (pin "2") (pinfunction "K_2") (pintype "passive"))
      (node (ref "D269") (pin "2") (pinfunction "K_2") (pintype "passive"))
    )
    (net (code "20") (name "/row5") (class "Default")
      (node (ref "D257") (pin "2") (pinfunction "K_2") (pintype "passive"))
      (node (ref "D258") (pin "2") (pinfunction "K_2") (pintype "passive"))
      (node (ref "D260") (pin "2") (pinfunction "K_2") (pintype "passive"))
      (node (ref "D262") (pin "2") (pinfunction "K_2") (pintype "passive"))
      (node (ref "D264") (pin "2") (pinfunction "K_2") (pintype "passive"))
      (node (ref "D265") (pin "2") (pinfunction "K_2") (pintype "passive"))
      (node (ref "D266") (pin "2") (pinfunction "K_2") (pintype "passive"))
    )
    (net (code "21") (name "Net-(D201-A)") (class "Default")
      (node (ref "D201") (pin "1") (pinfunction "A_1") (pintype "passive"))
      (node (ref "S201") (pin "1") (pinfunction "1_1") (pintype "passive"))
    )
    (net (code "22") (name "Net-(D202-A)") (class "Default")
      (node (ref "D202") (pin "1") (pinfunction "A_1") (pintype "passive"))
      (node (ref "S202") (pin "1") (pinfunction "1_1") (pintype "passive"))
    )
    (net (code "23") (name "Net-(D203-A)") (class "Default")
      (node (ref "D203") (pin "1") (pinfunction "A_1") (pintype "passive"))
      (node (ref "S203") (pin "1") (pinfunction "1_1") (pintype "passive"))
    )
    (net (code "24") (name "Net-(D204-A)") (class "Default")
      (node (ref "D204") (pin "1") (pinfunction "A_1") (pintype "passive"))
      (node (ref "S204") (pin "1") (pinfunction "1_1") (pintype "passive"))
    )
    (net (code "25") (name "Net-(D205-A)") (class "Default")
      (node (ref "D205") (pin "1") (pinfunction "A_1") (pintype "passive"))
      (node (ref "S205") (pin "1") (pinfunction "1_1") (pintype "passive"))
    )
    (net (code "26") (name "Net-(D206-A)") (class "Default")
      (node (ref "D206") (pin "1") (pinfunction "A_1") (pintype "passive"))
      (node (ref "S206") (pin "1") (pinfunction "1_1") (pintype "passive"))
    )
    (net (code "27") (name "Net-(D207-A)") (class "Default")
      (node (ref "D207") (pin "1") (pinfunction "A_1") (pintype "passive"))
      (node (ref "S207") (pin "1") (pinfunction "1_1") (pintype "passive"))
    )
    (net (code "28") (name "Net-(D208-A)") (class "Default")
      (node (ref "D208") (pin "1") (pinfunction "A_1") (pintype "passive"))
      (node (ref "S208") (pin "1") (pinfunction "1_1") (pintype "passive"))
    )
    (net (code "29") (name "Net-(D209-A)") (class "Default")
      (node (ref "D209") (pin "1") (pinfunction "A_1") (pintype "passive"))
      (node (ref "S209") (pin "1") (pinfunction "1_1") (pintype "passive"))
    )
    (net (code "30") (name "Net-(D210-A)") (class "Default")
      (node (ref "D210") (pin "1") (pinfunction "A_1") (pintype "passive"))
      (node (ref "S210") (pin "1") (pinfunction "1_1") (pintype "passive"))
    )
    (net (code "31") (name "Net-(D211-A)") (class "Default")
      (node (ref "D211") (pin "1") (pinfunction "A_1") (pintype "passive"))
      (node (ref "S211") (pin "1") (pinfunction "1_1") (pintype "passive"))
    )
    (net (code "32") (name "Net-(D212-A)") (class "Default")
      (node (ref "D212") (pin "1") (pinfunction "A_1") (pintype "passive"))
      (node (ref "S212") (pin "1") (pinfunction "1_1") (pintype "passive"))
    )
    (net (code "33") (name "Net-(D213-A)") (class "Default")
      (node (ref "D213") (pin "1") (pinfunction "A_1") (pintype "passive"))
      (node (ref "S213") (pin "1") (pinfunction "1_1") (pintype "passive"))
    )
    (net (code "34") (name "Net-(D214-A)") (class "Default")
      (node (ref "D214") (pin "1") (pinfunction "A_1") (pintype "passive"))
      (node (ref "S214") (pin "1") (pinfunction "1_1") (pintype "passive"))
    )
    (net (code "35") (name "Net-(D215-A)") (class "Default")
      (node (ref "D215") (pin "1") (pinfunction "A_1") (pintype "passive"))
      (node (ref "S215") (pin "1") (pinfunction "1_1") (pintype "passive"))
    )
    (net (code "36") (name "Net-(D216-A)") (class "Default")
      (node (ref "D216") (pin "1") (pinfunction "A_1") (pintype "passive"))
      (node (ref "S216") (pin "1") (pinfunction "1_1") (pintype "passive"))
    )
    (net (code "37") (name "Net-(D217-A)") (class "Default")
      (node (ref "D217") (pin "1") (pinfunction "A_1") (pintype "passive"))
      (node (ref "S217") (pin "1") (pinfunction "1_1") (pintype "passive"))
    )
    (net (code "38") (name "Net-(D218-A)") (class "Default")
      (node (ref "D218") (pin "1") (pinfunction "A_1") (pintype "passive"))
      (node (ref "S218") (pin "1") (pinfunction "1_1") (pintype "passive"))
    )
    (net (code "39") (name "Net-(D219-A)") (class "Default")
      (node (ref "D219") (pin "1") (pinfunction "A_1") (pintype "passive"))
      (node (ref "S219") (pin "1") (pinfunction "1_1") (pintype "passive"))
    )
    (net (code "40") (name "Net-(D220-A)") (class "Default")
      (node (ref "D220") (pin "1") (pinfunction "A_1") (pintype "passive"))
      (node (ref "S220") (pin "1") (pinfunction "1_1") (pintype "passive"))
    )
    (net (code "41") (name "Net-(D221-A)") (class "Default")
      (node (ref "D221") (pin "1") (pinfunction "A_1") (pintype "passive"))
      (node (ref "S221") (pin "1") (pinfunction "1_1") (pintype "passive"))
    )
    (net (code "42") (name "Net-(D222-A)") (class "Default")
      (node (ref "D222") (pin "1") (pinfunction "A_1") (pintype "passive"))
      (node (ref "S222") (pin "1") (pinfunction "1_1") (pintype "passive"))
    )
    (net (code "43") (name "Net-(D223-A)") (class "Default")
      (node (ref "D223") (pin "1") (pinfunction "A_1") (pintype "passive"))
      (node (ref "S223") (pin "1") (pinfunction "1_1") (pintype "passive"))
    )
    (net (code "44") (name "Net-(D224-A)") (class "Default")
      (node (ref "D224") (pin "1") (pinfunction "A_1") (pintype "passive"))
      (node (ref "S224") (pin "1") (pinfunction "1_1") (pintype "passive"))
    )
    (net (code "45") (name "Net-(D225-A)") (class "Default")
      (node (ref "D225") (pin "1") (pinfunction "A_1") (pintype "passive"))
      (node (ref "S225") (pin "1") (pinfunction "1_1") (pintype "passive"))
    )
    (net (code "46") (name "Net-(D226-A)") (class "Default")
      (node (ref "D226") (pin "1") (pinfunction "A_1") (pintype "passive"))
      (node (ref "S226") (pin "1") (pinfunction "1_1") (pintype "passive"))
    )
    (net (code "47") (name "Net-(D227-A)") (class "Default")
      (node (ref "D227") (pin "1") (pinfunction "A_1") (pintype "passive"))
      (node (ref "S227") (pin "1") (pinfunction "1_1") (pintype "passive"))
    )
    (net (code "48") (name "Net-(D228-A)") (class "Default")
      (node (ref "D228") (pin "1") (pinfunction "A_1") (pintype "passive"))
      (node (ref "S228") (pin "1") (pinfunction "1_1") (pintype "passive"))
    )
    (net (code "49") (name "Net-(D229-A)") (class "Default")
      (node (ref "D229") (pin "1") (pinfunction "A_1") (pintype "passive"))
      (node (ref "S229") (pin "1") (pinfunction "1_1") (pintype "passive"))
    )
    (net (code "50") (name "Net-(D230-A)") (class "Default")
      (node (ref "D230") (pin "1") (pinfunction "A_1") (pintype "passive"))
      (node (ref "S230") (pin "1") (pinfunction "1_1") (pintype "passive"))
    )
    (net (code "51") (name "Net-(D231-A)") (class "Default")
      (node (ref "D231") (pin "1") (pinfunction "A_1") (pintype "passive"))
      (node (ref "S231") (pin "1") (pinfunction "1_1") (pintype "passive"))
    )
    (net (code "52") (name "Net-(D232-A)") (class "Default")
      (node (ref "D232") (pin "1") (pinfunction "A_1") (pintype "passive"))
      (node (ref "S232") (pin "1") (pinfunction "1_1") (pintype "passive"))
    )
    (net (code "53") (name "Net-(D233-A)") (class "Default")
      (node (ref "D233") (pin "1") (pinfunction "A_1") (pintype "passive"))
      (node (ref "S233") (pin "1") (pinfunction "1_1") (pintype "passive"))
    )
    (net (code "54") (name "Net-(D234-A)") (class "Default")
      (node (ref "D234") (pin "1") (pinfunction "A_1") (pintype "passive"))
      (node (ref "S234") (pin "1") (pinfunction "1_1") (pintype "passive"))
    )
    (net (code "55") (name "Net-(D235-A)") (class "Default")
      (node (ref "D235") (pin "1") (pinfunction "A_1") (pintype "passive"))
      (node (ref "S235") (pin "1") (pinfunction "1_1") (pintype "passive"))
    )
    (net (code "56") (name "Net-(D236-A)") (class "Default")
      (node (ref "D236") (pin "1") (pinfunction "A_1") (pintype "passive"))
      (node (ref "S236") (pin "1") (pinfunction "1_1") (pintype "passive"))
    )
    (net (code "57") (name "Net-(D237-A)") (class "Default")
      (node (ref "D237") (pin "1") (pinfunction "A_1") (pintype "passive"))
      (node (ref "S237") (pin "1") (pinfunction "1_1") (pintype "passive"))
    )
    (net (code "58") (name "Net-(D238-A)") (class "Default")
      (node (ref "D238") (pin "1") (pinfunction "A_1") (pintype "passive"))
      (node (ref "S238") (pin "1") (pinfunction "1_1") (pintype "passive"))
    )
    (net (code "59") (name "Net-(D239-A)") (class "Default")
      (node (ref "D239") (pin "1") (pinfunction "A_1") (pintype "passive"))
      (node (ref "S239") (pin "1") (pinfunction "1_1") (pintype "passive"))
    )
    (net (code "60") (name "Net-(D240-A)") (class "Default")
      (node (ref "D240") (pin "1") (pinfunction "A_1") (pintype "passive"))
      (node (ref "S240") (pin "1") (pinfunction "1_1") (pintype "passive"))
    )
    (net (code "61") (name "Net-(D242-A)") (class "Default")
      (node (ref "D242") (pin "1") (pinfunction "A_1") (pintype "passive"))
      (node (ref "S242") (pin "1") (pinfunction "1_1") (pintype "passive"))
    )
    (net (code "62") (name "Net-(D243-A)") (class "Default")
      (node (ref "D243") (pin "1") (pinfunction "A_1") (pintype "passive"))
      (node (ref "S243") (pin "1") (pinfunction "1_1") (pintype "passive"))
    )
    (net (code "63") (name "Net-(D245-A)") (class "Default")
      (node (ref "D245") (pin "1") (pinfunction "A_1") (pintype "passive"))
      (node (ref "S245") (pin "1") (pinfunction "1_1") (pintype "passive"))
    )
    (net (code "64") (name "Net-(D246-A)") (class "Default")
      (node (ref "D246") (pin "1") (pinfunction "A_1") (pintype "passive"))
      (node (ref "S246") (pin "1") (pinfunction "1_1") (pintype "passive"))
    )
    (net (code "65") (name "Net-(D247-A)") (class "Default")
      (node (ref "D247") (pin "1") (pinfunction "A_1") (pintype "passive"))
      (node (ref "S247") (pin "1") (pinfunction "1_1") (pintype "passive"))
    )
    (net (code "66") (name "Net-(D248-A)") (class "Default")
      (node (ref "D248") (pin "1") (pinfunction "A_1") (pintype "passive"))
      (node (ref "S248") (pin "1") (pinfunction "1_1") (pintype "passive"))
    )
    (net (code "67") (name "Net-(D249-A)") (class "Default")
      (node (ref "D249") (pin "1") (pinfunction "A_1") (pintype "passive"))
      (node (ref "S249") (pin "1") (pinfunction "1_1") (pintype "passive"))
    )
    (net (code "68") (name "Net-(D250-A)") (class "Default")
      (node (ref "D250") (pin "1") (pinfunction "A_1") (pintype "passive"))
      (node (ref "S250") (pin "1") (pinfunction "1_1") (pintype "passive"))
    )
    (net (code "69") (name "Net-(D251-A)") (class "Default")
      (node (ref "D251") (pin "1") (pinfunction "A_1") (pintype "passive"))
      (node (ref "S251") (pin "1") (pinfunction "1_1") (pintype "passive"))
    )
    (net (code "70") (name "Net-(D252-A)") (class "Default")
      (node (ref "D252") (pin "1") (pinfunction "A_1") (pintype "passive"))
      (node (ref "S252") (pin "1") (pinfunction "1_1") (pintype "passive"))
    )
    (net (code "71") (name "Net-(D253-A)") (class "Default")
      (node (ref "D253") (pin "1") (pinfunction "A_1") (pintype "passive"))
      (node (ref "S253") (pin "1") (pinfunction "1_1") (pintype "passive"))
    )
    (net (code "72") (name "Net-(D254-A)") (class "Default")
      (node (ref "D254") (pin "1") (pinfunction "A_1") (pintype "passive"))
      (node (ref "S254") (pin "1") (pinfunction "1_1") (pintype "passive"))
    )
    (net (code "73") (name "Net-(D256-A)") (class "Default")
      (node (ref "D256") (pin "1") (pinfunction "A_1") (pintype "passive"))
      (node (ref "S256") (pin "1") (pinfunction "1_1") (pintype "passive"))
    )
    (net (code "74") (name "Net-(D257-A)") (class "Default")
      (node (ref "D257") (pin "1") (pinfunction "A_1") (pintype "passive"))
      (node (ref "S257") (pin "1") (pinfunction "1_1") (pintype "passive"))
    )
    (net (code "75") (name "Net-(D258-A)") (class "Default")
      (node (ref "D258") (pin "1") (pinfunction "A_1") (pintype "passive"))
      (node (ref "S258") (pin "1") (pinfunction "1_1") (pintype "passive"))
    )
    (net (code "76") (name "Net-(D259-A)") (class "Default")
      (node (ref "D259") (pin "1") (pinfunction "A_1") (pintype "passive"))
      (node (ref "S259") (pin "1") (pinfunction "1_1") (pintype "passive"))
    )
    (net (code "77") (name "Net-(D260-A)") (class "Default")
      (node (ref "D260") (pin "1") (pinfunction "A_1") (pintype "passive"))
      (node (ref "S260") (pin "1") (pinfunction "1_1") (pintype "passive"))
    )
    (net (code "78") (name "Net-(D262-A)") (class "Default")
      (node (ref "D262") (pin "1") (pinfunction "A_1") (pintype "passive"))
      (node (ref "S262") (pin "1") (pinfunction "1_1") (pintype "passive"))
    )
    (net (code "79") (name "Net-(D264-A)") (class "Default")
      (node (ref "D264") (pin "1") (pinfunction "A_1") (pintype "passive"))
      (node (ref "S264") (pin "1") (pinfunction "1_1") (pintype "passive"))
    )
    (net (code "80") (name "Net-(D265-A)") (class "Default")
      (node (ref "D265") (pin "1") (pinfunction "A_1") (pintype "passive"))
      (node (ref "S265") (pin "1") (pinfunction "1_1") (pintype "passive"))
    )
    (net (code "81") (name "Net-(D266-A)") (class "Default")
      (node (ref "D266") (pin "1") (pinfunction "A_1") (pintype "passive"))
      (node (ref "S266") (pin "1") (pinfunction "1_1") (pintype "passive"))
    )
    (net (code "82") (name "Net-(D269-A)") (class "Default")
      (node (ref "D269") (pin "1") (pinfunction "A_1") (pintype "passive"))
      (node (ref "S269") (pin "1") (pinfunction "1_1") (pintype "passive"))
    )
  )
)
